# SCH_Brake_chopper_circuit_BissC.net
KiCad netlist of a schematic drawn in EasyEDA
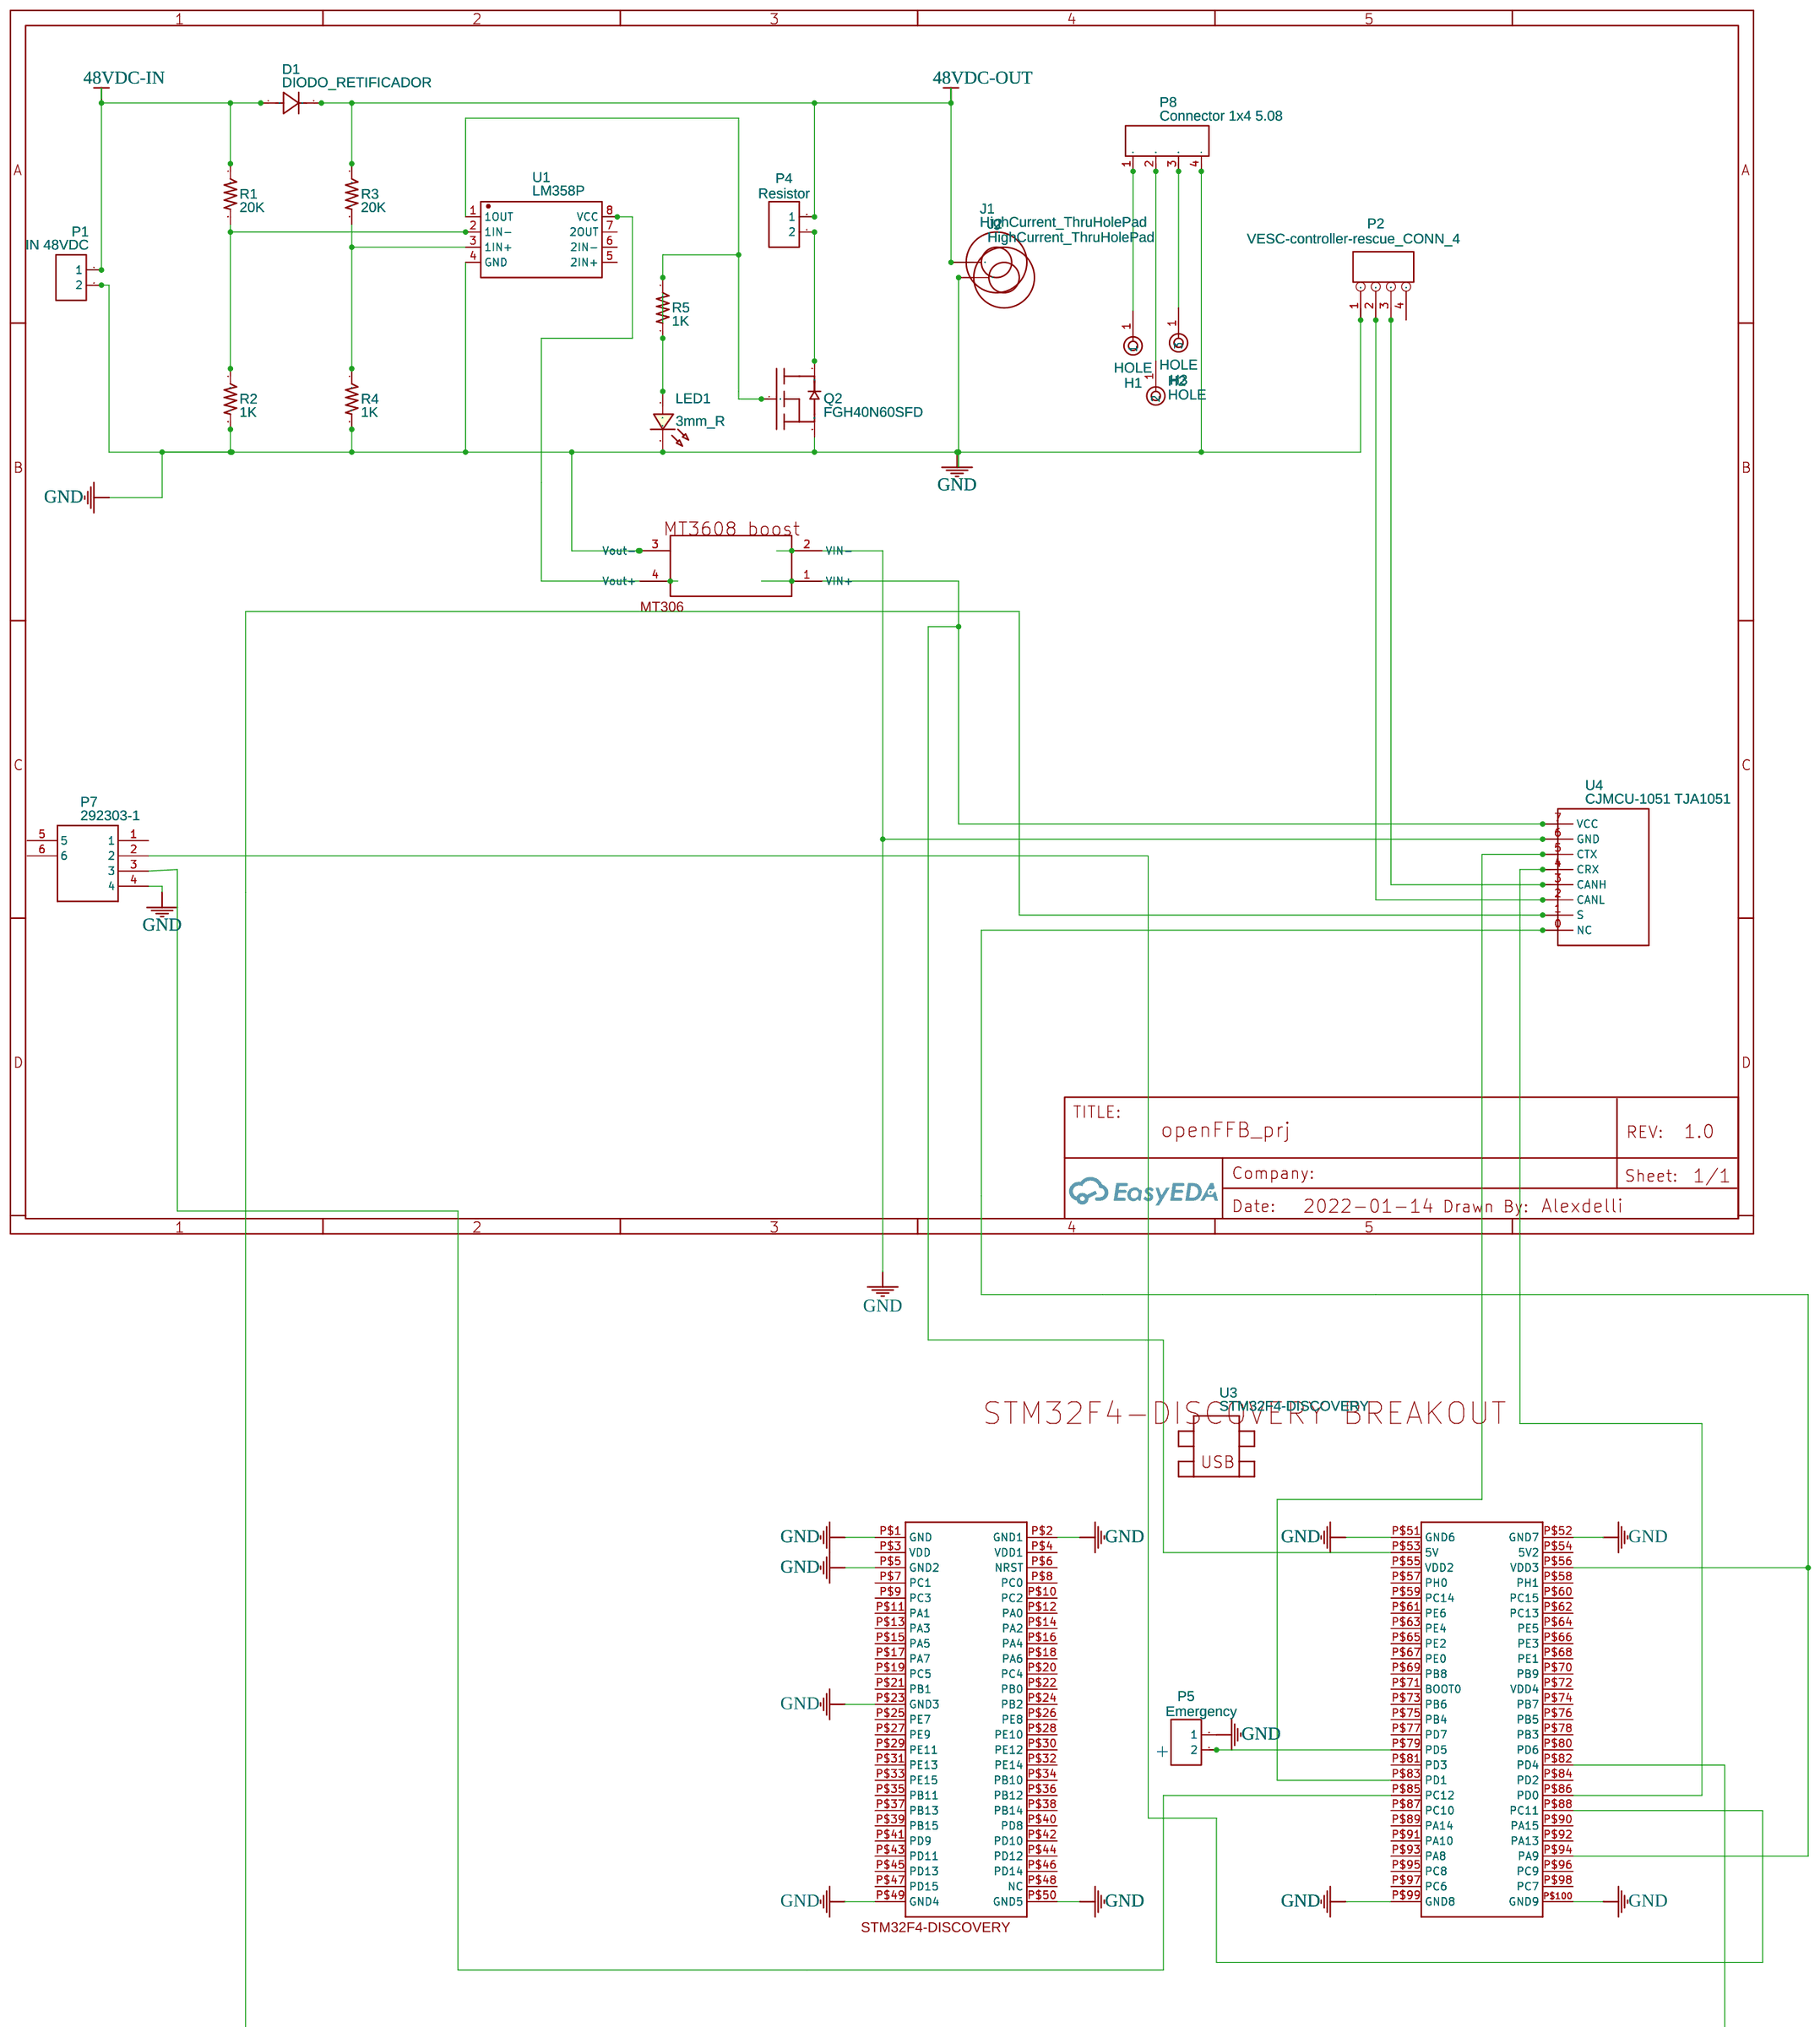
[diagram p0: schematic sheet]

(export (version "E")
  (design (tool "Eeschema 10.0.6"))
  (components
    (comp (ref "D1") (value "DIODO_RETIFICADOR") (libsource (lib "") (part "DIODO_RETIFICADOR")))
    (comp (ref "H1") (value "HOLE") (libsource (lib "") (part "HOLE_2")))
    (comp (ref "H2") (value "HOLE") (libsource (lib "") (part "HOLE")))
    (comp (ref "H3") (value "HOLE") (libsource (lib "") (part "HOLE_1")))
    (comp (ref "J1") (value "HighCurrent_ThruHolePad") (libsource (lib "") (part "HighCurrent_ThruHolePad")))
    (comp (ref "J2") (value "HighCurrent_ThruHolePad") (libsource (lib "") (part "HighCurrent_ThruHolePad")))
    (comp (ref "LED1")
      (value "3mm_R")
      (fields
        (field (name "BOM_Manufacturer Part") "204-10SDRD/S530-A3-L")
        (field (name "BOM_Supplier Part") "C84774")
      )
      (libsource (lib "") (part "LED-TH-3mm_R"))
    )
    (comp (ref "P1") (value "IN 48VDC") (libsource (lib "") (part "CONN-TH_2P-P5.08")))
    (comp (ref "P2")
      (value "VESC-controller-rescue_CONN_4")
      (libsource (lib "") (part "VESC-controller-rescue_CONN_4"))
    )
    (comp (ref "P4") (value "Resistor") (libsource (lib "") (part "CONN-TH_2P-P5.08_1")))
    (comp (ref "P5") (value "Emergency") (libsource (lib "") (part "CONN-TH_2P-P5.08_1")))
    (comp (ref "P7") (value "292303-1") (libsource (lib "") (part "292303-1")))
    (comp (ref "P8") (value "Connector 1x4 5.08") (libsource (lib "") (part "Connector 1x4 5.08")))
    (comp (ref "Q2")
      (value "FGH40N60SFD")
      (fields (field (name "BOM_Supplier Part") "C898160"))
      (libsource (lib "") (part "FGH40N60SFD"))
    )
    (comp (ref "R1") (value "20K") (libsource (lib "") (part "Resistor")))
    (comp (ref "R2") (value "1K") (libsource (lib "") (part "Resistor")))
    (comp (ref "R3") (value "20K") (libsource (lib "") (part "Resistor")))
    (comp (ref "R4") (value "1K") (libsource (lib "") (part "Resistor")))
    (comp (ref "R5") (value "1K") (libsource (lib "") (part "Resistor")))
    (comp (ref "U1")
      (value "LM358P")
      (fields (field (name "BOM_Supplier Part") "C5213"))
      (libsource (lib "") (part "LM358P"))
    )
    (comp (ref "U2") (value "mt306 boost") (libsource (lib "") (part "mt306 boost")))
    (comp (ref "U3") (value "STM32F4-DISCOVERY") (libsource (lib "") (part "STM32F4-DISCOVERY")))
    (comp (ref "U4")
      (value "CJMCU-1051 TJA1051")
      (fields (field (name "BOM_Manufacturer Part") "TJA1051"))
      (libsource (lib "") (part "CJMCU-1051 TJA1051"))
    )
  )
  (nets
    (net (code "1") (name "48VDC-IN") (class "Default")
      (node (ref "D1") (pin "A") (pinfunction "A_A") (pintype "unspecified"))
      (node (ref "P1") (pin "1") (pinfunction "1_1") (pintype "unspecified"))
      (node (ref "R1") (pin "1") (pinfunction "1_1") (pintype "unspecified"))
    )
    (net (code "2") (name "48VDC-OUT") (class "Default")
      (node (ref "D1") (pin "K") (pinfunction "K_K") (pintype "unspecified"))
      (node (ref "J1") (pin "1") (pinfunction "1_1") (pintype "unspecified"))
      (node (ref "P4") (pin "2") (pinfunction "1_2") (pintype "unspecified"))
      (node (ref "R3") (pin "1") (pinfunction "1_1") (pintype "unspecified"))
    )
    (net (code "3") (name "GND") (class "Default")
      (node (ref "J2") (pin "1") (pinfunction "1_1") (pintype "unspecified"))
      (node (ref "LED1") (pin "2") (pinfunction "2_2") (pintype "unspecified"))
      (node (ref "P1") (pin "2") (pinfunction "2_2") (pintype "unspecified"))
      (node (ref "P2") (pin "1") (pinfunction "P1_1") (pintype "unspecified"))
      (node (ref "P5") (pin "2") (pinfunction "1_2") (pintype "unspecified"))
      (node (ref "P7") (pin "4") (pinfunction "4_4") (pintype "bidirectional"))
      (node (ref "P8") (pin "4") (pinfunction "4_4") (pintype "unspecified"))
      (node (ref "Q2") (pin "3") (pinfunction "S_3") (pintype "unspecified"))
      (node (ref "R2") (pin "2") (pinfunction "2_2") (pintype "unspecified"))
      (node (ref "R4") (pin "2") (pinfunction "2_2") (pintype "unspecified"))
      (node (ref "U1") (pin "4") (pinfunction "GND_4") (pintype "unspecified"))
      (node (ref "U2") (pin "2") (pinfunction "VIN-_2") (pintype "unspecified"))
      (node (ref "U2") (pin "3") (pinfunction "Vout-_3") (pintype "unspecified"))
      (node (ref "U3") (pin "P$1") (pinfunction "GND_P$1") (pintype "unspecified"))
      (node (ref "U3") (pin "P$100") (pinfunction "GND9_P$100") (pintype "unspecified"))
      (node (ref "U3") (pin "P$2") (pinfunction "GND1_P$2") (pintype "unspecified"))
      (node (ref "U3") (pin "P$23") (pinfunction "GND3_P$23") (pintype "unspecified"))
      (node (ref "U3") (pin "P$49") (pinfunction "GND4_P$49") (pintype "unspecified"))
      (node (ref "U3") (pin "P$5") (pinfunction "GND2_P$5") (pintype "unspecified"))
      (node (ref "U3") (pin "P$50") (pinfunction "GND5_P$50") (pintype "unspecified"))
      (node (ref "U3") (pin "P$51") (pinfunction "GND6_P$51") (pintype "unspecified"))
      (node (ref "U3") (pin "P$52") (pinfunction "GND7_P$52") (pintype "unspecified"))
      (node (ref "U3") (pin "P$99") (pinfunction "GND8_P$99") (pintype "unspecified"))
      (node (ref "U4") (pin "6") (pinfunction "GND_6") (pintype "unspecified"))
    )
    (net (code "4") (name "Net-(H1-Pad1)") (class "Default")
      (node (ref "H1") (pin "1") (pinfunction "1_1") (pintype "unspecified"))
      (node (ref "P8") (pin "1") (pinfunction "1_1") (pintype "unspecified"))
    )
    (net (code "5") (name "Net-(H2-2)") (class "Default")
      (node (ref "H2") (pin "1") (pinfunction "2_1") (pintype "unspecified"))
      (node (ref "P8") (pin "2") (pinfunction "2_2") (pintype "unspecified"))
    )
    (net (code "6") (name "Net-(H3-3)") (class "Default")
      (node (ref "H3") (pin "1") (pinfunction "3_1") (pintype "unspecified"))
      (node (ref "P8") (pin "3") (pinfunction "3_3") (pintype "unspecified"))
    )
    (net (code "7") (name "Net-(LED1-Pad1)") (class "Default")
      (node (ref "LED1") (pin "1") (pinfunction "1_1") (pintype "unspecified"))
      (node (ref "R5") (pin "2") (pinfunction "2_2") (pintype "unspecified"))
    )
    (net (code "8") (name "Net-(P2-P2)") (class "Default")
      (node (ref "P2") (pin "2") (pinfunction "P2_2") (pintype "unspecified"))
      (node (ref "U4") (pin "2") (pinfunction "CANL_2") (pintype "unspecified"))
    )
    (net (code "9") (name "Net-(P2-P3)") (class "Default")
      (node (ref "P2") (pin "3") (pinfunction "P3_3") (pintype "unspecified"))
      (node (ref "U4") (pin "3") (pinfunction "CANH_3") (pintype "unspecified"))
    )
    (net (code "10") (name "Net-(P4-2)") (class "Default")
      (node (ref "P4") (pin "1") (pinfunction "2_1") (pintype "unspecified"))
      (node (ref "Q2") (pin "2") (pinfunction "D_2") (pintype "unspecified"))
    )
    (net (code "11") (name "Net-(P5-2)") (class "Default")
      (node (ref "P5") (pin "1") (pinfunction "2_1") (pintype "unspecified"))
      (node (ref "U3") (pin "P$79") (pinfunction "PD5_P$79") (pintype "unspecified"))
    )
    (net (code "12") (name "Net-(Q2-G)") (class "Default")
      (node (ref "Q2") (pin "1") (pinfunction "G_1") (pintype "unspecified"))
      (node (ref "R5") (pin "1") (pinfunction "1_1") (pintype "unspecified"))
      (node (ref "U1") (pin "1") (pinfunction "1OUT_1") (pintype "unspecified"))
    )
    (net (code "13") (name "Net-(U1-1IN+)") (class "Default")
      (node (ref "R3") (pin "2") (pinfunction "2_2") (pintype "unspecified"))
      (node (ref "R4") (pin "1") (pinfunction "1_1") (pintype "unspecified"))
      (node (ref "U1") (pin "3") (pinfunction "1IN+_3") (pintype "unspecified"))
    )
    (net (code "14") (name "Net-(U1-1IN-)") (class "Default")
      (node (ref "R1") (pin "2") (pinfunction "2_2") (pintype "unspecified"))
      (node (ref "R2") (pin "1") (pinfunction "1_1") (pintype "unspecified"))
      (node (ref "U1") (pin "2") (pinfunction "1IN-_2") (pintype "unspecified"))
    )
    (net (code "15") (name "Net-(U1-VCC)") (class "Default")
      (node (ref "U1") (pin "8") (pinfunction "VCC_8") (pintype "unspecified"))
      (node (ref "U2") (pin "4") (pinfunction "Vout+_4") (pintype "unspecified"))
    )
    (net (code "16") (name "Net-(U2-VIN+)") (class "Default")
      (node (ref "U2") (pin "1") (pinfunction "VIN+_1") (pintype "unspecified"))
      (node (ref "U3") (pin "P$53") (pinfunction "5V_P$53") (pintype "unspecified"))
      (node (ref "U4") (pin "7") (pinfunction "VCC_7") (pintype "unspecified"))
    )
    (net (code "17") (name "Net-(U3-PA9)") (class "Default")
      (node (ref "U3") (pin "P$56") (pinfunction "VDD3_P$56") (pintype "unspecified"))
      (node (ref "U3") (pin "P$94") (pinfunction "PA9_P$94") (pintype "unspecified"))
      (node (ref "U4") (pin "0") (pinfunction "NC_0") (pintype "unspecified"))
    )
    (net (code "18") (name "Net-(U3-PC11)") (class "Default")
      (node (ref "P7") (pin "2") (pinfunction "2_2") (pintype "bidirectional"))
      (node (ref "U3") (pin "P$88") (pinfunction "PC11_P$88") (pintype "unspecified"))
    )
    (net (code "19") (name "Net-(U3-PC12)") (class "Default")
      (node (ref "P7") (pin "3") (pinfunction "3_3") (pintype "bidirectional"))
      (node (ref "U3") (pin "P$85") (pinfunction "PC12_P$85") (pintype "unspecified"))
    )
    (net (code "20") (name "Net-(U3-PD0)") (class "Default")
      (node (ref "U3") (pin "P$86") (pinfunction "PD0_P$86") (pintype "unspecified"))
      (node (ref "U4") (pin "4") (pinfunction "CRX_4") (pintype "unspecified"))
    )
    (net (code "21") (name "Net-(U3-PD1)") (class "Default")
      (node (ref "U3") (pin "P$83") (pinfunction "PD1_P$83") (pintype "unspecified"))
      (node (ref "U4") (pin "5") (pinfunction "CTX_5") (pintype "unspecified"))
    )
    (net (code "22") (name "Net-(U3-PD4)") (class "Default")
      (node (ref "U3") (pin "P$82") (pinfunction "PD4_P$82") (pintype "unspecified"))
      (node (ref "U4") (pin "1") (pinfunction "S_1") (pintype "unspecified"))
    )
    (net (code "23") (name "unconnected-(P2-P4-Pad4)") (class "Default")
      (node (ref "P2") (pin "4") (pinfunction "P4_4") (pintype "unspecified"))
    )
    (net (code "24") (name "unconnected-(P7-Pad1)") (class "Default")
      (node (ref "P7") (pin "1") (pinfunction "1_1") (pintype "bidirectional"))
    )
    (net (code "25") (name "unconnected-(P7-Pad5)") (class "Default")
      (node (ref "P7") (pin "5") (pinfunction "5_5") (pintype "bidirectional"))
    )
    (net (code "26") (name "unconnected-(P7-Pad6)") (class "Default")
      (node (ref "P7") (pin "6") (pinfunction "6_6") (pintype "bidirectional"))
    )
    (net (code "27") (name "unconnected-(U1-2IN+-Pad5)") (class "Default")
      (node (ref "U1") (pin "5") (pinfunction "2IN+_5") (pintype "unspecified"))
    )
    (net (code "28") (name "unconnected-(U1-2IN--Pad6)") (class "Default")
      (node (ref "U1") (pin "6") (pinfunction "2IN-_6") (pintype "unspecified"))
    )
    (net (code "29") (name "unconnected-(U1-2OUT-Pad7)") (class "Default")
      (node (ref "U1") (pin "7") (pinfunction "2OUT_7") (pintype "unspecified"))
    )
    (net (code "30") (name "unconnected-(U3-5V2-PadP$54)") (class "Default")
      (node (ref "U3") (pin "P$54") (pinfunction "5V2_P$54") (pintype "unspecified"))
    )
    (net (code "31") (name "unconnected-(U3-BOOT0-PadP$71)") (class "Default")
      (node (ref "U3") (pin "P$71") (pinfunction "BOOT0_P$71") (pintype "unspecified"))
    )
    (net (code "32") (name "unconnected-(U3-NC-PadP$48)") (class "Default")
      (node (ref "U3") (pin "P$48") (pinfunction "NC_P$48") (pintype "unspecified"))
    )
    (net (code "33") (name "unconnected-(U3-NRST-PadP$6)") (class "Default")
      (node (ref "U3") (pin "P$6") (pinfunction "NRST_P$6") (pintype "unspecified"))
    )
    (net (code "34") (name "unconnected-(U3-PA0-PadP$12)") (class "Default")
      (node (ref "U3") (pin "P$12") (pinfunction "PA0_P$12") (pintype "unspecified"))
    )
    (net (code "35") (name "unconnected-(U3-PA1-PadP$11)") (class "Default")
      (node (ref "U3") (pin "P$11") (pinfunction "PA1_P$11") (pintype "unspecified"))
    )
    (net (code "36") (name "unconnected-(U3-PA2-PadP$14)") (class "Default")
      (node (ref "U3") (pin "P$14") (pinfunction "PA2_P$14") (pintype "unspecified"))
    )
    (net (code "37") (name "unconnected-(U3-PA3-PadP$13)") (class "Default")
      (node (ref "U3") (pin "P$13") (pinfunction "PA3_P$13") (pintype "unspecified"))
    )
    (net (code "38") (name "unconnected-(U3-PA4-PadP$16)") (class "Default")
      (node (ref "U3") (pin "P$16") (pinfunction "PA4_P$16") (pintype "unspecified"))
    )
    (net (code "39") (name "unconnected-(U3-PA5-PadP$15)") (class "Default")
      (node (ref "U3") (pin "P$15") (pinfunction "PA5_P$15") (pintype "unspecified"))
    )
    (net (code "40") (name "unconnected-(U3-PA6-PadP$18)") (class "Default")
      (node (ref "U3") (pin "P$18") (pinfunction "PA6_P$18") (pintype "unspecified"))
    )
    (net (code "41") (name "unconnected-(U3-PA7-PadP$17)") (class "Default")
      (node (ref "U3") (pin "P$17") (pinfunction "PA7_P$17") (pintype "unspecified"))
    )
    (net (code "42") (name "unconnected-(U3-PA8-PadP$93)") (class "Default")
      (node (ref "U3") (pin "P$93") (pinfunction "PA8_P$93") (pintype "unspecified"))
    )
    (net (code "43") (name "unconnected-(U3-PA10-PadP$91)") (class "Default")
      (node (ref "U3") (pin "P$91") (pinfunction "PA10_P$91") (pintype "unspecified"))
    )
    (net (code "44") (name "unconnected-(U3-PA13-PadP$92)") (class "Default")
      (node (ref "U3") (pin "P$92") (pinfunction "PA13_P$92") (pintype "unspecified"))
    )
    (net (code "45") (name "unconnected-(U3-PA14-PadP$89)") (class "Default")
      (node (ref "U3") (pin "P$89") (pinfunction "PA14_P$89") (pintype "unspecified"))
    )
    (net (code "46") (name "unconnected-(U3-PA15-PadP$90)") (class "Default")
      (node (ref "U3") (pin "P$90") (pinfunction "PA15_P$90") (pintype "unspecified"))
    )
    (net (code "47") (name "unconnected-(U3-PB0-PadP$22)") (class "Default")
      (node (ref "U3") (pin "P$22") (pinfunction "PB0_P$22") (pintype "unspecified"))
    )
    (net (code "48") (name "unconnected-(U3-PB1-PadP$21)") (class "Default")
      (node (ref "U3") (pin "P$21") (pinfunction "PB1_P$21") (pintype "unspecified"))
    )
    (net (code "49") (name "unconnected-(U3-PB2-PadP$24)") (class "Default")
      (node (ref "U3") (pin "P$24") (pinfunction "PB2_P$24") (pintype "unspecified"))
    )
    (net (code "50") (name "unconnected-(U3-PB3-PadP$78)") (class "Default")
      (node (ref "U3") (pin "P$78") (pinfunction "PB3_P$78") (pintype "unspecified"))
    )
    (net (code "51") (name "unconnected-(U3-PB4-PadP$75)") (class "Default")
      (node (ref "U3") (pin "P$75") (pinfunction "PB4_P$75") (pintype "unspecified"))
    )
    (net (code "52") (name "unconnected-(U3-PB5-PadP$76)") (class "Default")
      (node (ref "U3") (pin "P$76") (pinfunction "PB5_P$76") (pintype "unspecified"))
    )
    (net (code "53") (name "unconnected-(U3-PB6-PadP$73)") (class "Default")
      (node (ref "U3") (pin "P$73") (pinfunction "PB6_P$73") (pintype "unspecified"))
    )
    (net (code "54") (name "unconnected-(U3-PB7-PadP$74)") (class "Default")
      (node (ref "U3") (pin "P$74") (pinfunction "PB7_P$74") (pintype "unspecified"))
    )
    (net (code "55") (name "unconnected-(U3-PB8-PadP$69)") (class "Default")
      (node (ref "U3") (pin "P$69") (pinfunction "PB8_P$69") (pintype "unspecified"))
    )
    (net (code "56") (name "unconnected-(U3-PB9-PadP$70)") (class "Default")
      (node (ref "U3") (pin "P$70") (pinfunction "PB9_P$70") (pintype "unspecified"))
    )
    (net (code "57") (name "unconnected-(U3-PB10-PadP$34)") (class "Default")
      (node (ref "U3") (pin "P$34") (pinfunction "PB10_P$34") (pintype "unspecified"))
    )
    (net (code "58") (name "unconnected-(U3-PB11-PadP$35)") (class "Default")
      (node (ref "U3") (pin "P$35") (pinfunction "PB11_P$35") (pintype "unspecified"))
    )
    (net (code "59") (name "unconnected-(U3-PB12-PadP$36)") (class "Default")
      (node (ref "U3") (pin "P$36") (pinfunction "PB12_P$36") (pintype "unspecified"))
    )
    (net (code "60") (name "unconnected-(U3-PB13-PadP$37)") (class "Default")
      (node (ref "U3") (pin "P$37") (pinfunction "PB13_P$37") (pintype "unspecified"))
    )
    (net (code "61") (name "unconnected-(U3-PB14-PadP$38)") (class "Default")
      (node (ref "U3") (pin "P$38") (pinfunction "PB14_P$38") (pintype "unspecified"))
    )
    (net (code "62") (name "unconnected-(U3-PB15-PadP$39)") (class "Default")
      (node (ref "U3") (pin "P$39") (pinfunction "PB15_P$39") (pintype "unspecified"))
    )
    (net (code "63") (name "unconnected-(U3-PC0-PadP$8)") (class "Default")
      (node (ref "U3") (pin "P$8") (pinfunction "PC0_P$8") (pintype "unspecified"))
    )
    (net (code "64") (name "unconnected-(U3-PC1-PadP$7)") (class "Default")
      (node (ref "U3") (pin "P$7") (pinfunction "PC1_P$7") (pintype "unspecified"))
    )
    (net (code "65") (name "unconnected-(U3-PC2-PadP$10)") (class "Default")
      (node (ref "U3") (pin "P$10") (pinfunction "PC2_P$10") (pintype "unspecified"))
    )
    (net (code "66") (name "unconnected-(U3-PC3-PadP$9)") (class "Default")
      (node (ref "U3") (pin "P$9") (pinfunction "PC3_P$9") (pintype "unspecified"))
    )
    (net (code "67") (name "unconnected-(U3-PC4-PadP$20)") (class "Default")
      (node (ref "U3") (pin "P$20") (pinfunction "PC4_P$20") (pintype "unspecified"))
    )
    (net (code "68") (name "unconnected-(U3-PC5-PadP$19)") (class "Default")
      (node (ref "U3") (pin "P$19") (pinfunction "PC5_P$19") (pintype "unspecified"))
    )
    (net (code "69") (name "unconnected-(U3-PC6-PadP$97)") (class "Default")
      (node (ref "U3") (pin "P$97") (pinfunction "PC6_P$97") (pintype "unspecified"))
    )
    (net (code "70") (name "unconnected-(U3-PC7-PadP$98)") (class "Default")
      (node (ref "U3") (pin "P$98") (pinfunction "PC7_P$98") (pintype "unspecified"))
    )
    (net (code "71") (name "unconnected-(U3-PC8-PadP$95)") (class "Default")
      (node (ref "U3") (pin "P$95") (pinfunction "PC8_P$95") (pintype "unspecified"))
    )
    (net (code "72") (name "unconnected-(U3-PC9-PadP$96)") (class "Default")
      (node (ref "U3") (pin "P$96") (pinfunction "PC9_P$96") (pintype "unspecified"))
    )
    (net (code "73") (name "unconnected-(U3-PC10-PadP$87)") (class "Default")
      (node (ref "U3") (pin "P$87") (pinfunction "PC10_P$87") (pintype "unspecified"))
    )
    (net (code "74") (name "unconnected-(U3-PC13-PadP$62)") (class "Default")
      (node (ref "U3") (pin "P$62") (pinfunction "PC13_P$62") (pintype "unspecified"))
    )
    (net (code "75") (name "unconnected-(U3-PC14-PadP$59)") (class "Default")
      (node (ref "U3") (pin "P$59") (pinfunction "PC14_P$59") (pintype "unspecified"))
    )
    (net (code "76") (name "unconnected-(U3-PC15-PadP$60)") (class "Default")
      (node (ref "U3") (pin "P$60") (pinfunction "PC15_P$60") (pintype "unspecified"))
    )
    (net (code "77") (name "unconnected-(U3-PD2-PadP$84)") (class "Default")
      (node (ref "U3") (pin "P$84") (pinfunction "PD2_P$84") (pintype "unspecified"))
    )
    (net (code "78") (name "unconnected-(U3-PD3-PadP$81)") (class "Default")
      (node (ref "U3") (pin "P$81") (pinfunction "PD3_P$81") (pintype "unspecified"))
    )
    (net (code "79") (name "unconnected-(U3-PD6-PadP$80)") (class "Default")
      (node (ref "U3") (pin "P$80") (pinfunction "PD6_P$80") (pintype "unspecified"))
    )
    (net (code "80") (name "unconnected-(U3-PD7-PadP$77)") (class "Default")
      (node (ref "U3") (pin "P$77") (pinfunction "PD7_P$77") (pintype "unspecified"))
    )
    (net (code "81") (name "unconnected-(U3-PD8-PadP$40)") (class "Default")
      (node (ref "U3") (pin "P$40") (pinfunction "PD8_P$40") (pintype "unspecified"))
    )
    (net (code "82") (name "unconnected-(U3-PD9-PadP$41)") (class "Default")
      (node (ref "U3") (pin "P$41") (pinfunction "PD9_P$41") (pintype "unspecified"))
    )
    (net (code "83") (name "unconnected-(U3-PD10-PadP$42)") (class "Default")
      (node (ref "U3") (pin "P$42") (pinfunction "PD10_P$42") (pintype "unspecified"))
    )
    (net (code "84") (name "unconnected-(U3-PD11-PadP$43)") (class "Default")
      (node (ref "U3") (pin "P$43") (pinfunction "PD11_P$43") (pintype "unspecified"))
    )
    (net (code "85") (name "unconnected-(U3-PD12-PadP$44)") (class "Default")
      (node (ref "U3") (pin "P$44") (pinfunction "PD12_P$44") (pintype "unspecified"))
    )
    (net (code "86") (name "unconnected-(U3-PD13-PadP$45)") (class "Default")
      (node (ref "U3") (pin "P$45") (pinfunction "PD13_P$45") (pintype "unspecified"))
    )
    (net (code "87") (name "unconnected-(U3-PD14-PadP$46)") (class "Default")
      (node (ref "U3") (pin "P$46") (pinfunction "PD14_P$46") (pintype "unspecified"))
    )
    (net (code "88") (name "unconnected-(U3-PD15-PadP$47)") (class "Default")
      (node (ref "U3") (pin "P$47") (pinfunction "PD15_P$47") (pintype "unspecified"))
    )
    (net (code "89") (name "unconnected-(U3-PE0-PadP$67)") (class "Default")
      (node (ref "U3") (pin "P$67") (pinfunction "PE0_P$67") (pintype "unspecified"))
    )
    (net (code "90") (name "unconnected-(U3-PE1-PadP$68)") (class "Default")
      (node (ref "U3") (pin "P$68") (pinfunction "PE1_P$68") (pintype "unspecified"))
    )
    (net (code "91") (name "unconnected-(U3-PE2-PadP$65)") (class "Default")
      (node (ref "U3") (pin "P$65") (pinfunction "PE2_P$65") (pintype "unspecified"))
    )
    (net (code "92") (name "unconnected-(U3-PE3-PadP$66)") (class "Default")
      (node (ref "U3") (pin "P$66") (pinfunction "PE3_P$66") (pintype "unspecified"))
    )
    (net (code "93") (name "unconnected-(U3-PE4-PadP$63)") (class "Default")
      (node (ref "U3") (pin "P$63") (pinfunction "PE4_P$63") (pintype "unspecified"))
    )
    (net (code "94") (name "unconnected-(U3-PE5-PadP$64)") (class "Default")
      (node (ref "U3") (pin "P$64") (pinfunction "PE5_P$64") (pintype "unspecified"))
    )
    (net (code "95") (name "unconnected-(U3-PE6-PadP$61)") (class "Default")
      (node (ref "U3") (pin "P$61") (pinfunction "PE6_P$61") (pintype "unspecified"))
    )
    (net (code "96") (name "unconnected-(U3-PE7-PadP$25)") (class "Default")
      (node (ref "U3") (pin "P$25") (pinfunction "PE7_P$25") (pintype "unspecified"))
    )
    (net (code "97") (name "unconnected-(U3-PE8-PadP$26)") (class "Default")
      (node (ref "U3") (pin "P$26") (pinfunction "PE8_P$26") (pintype "unspecified"))
    )
    (net (code "98") (name "unconnected-(U3-PE9-PadP$27)") (class "Default")
      (node (ref "U3") (pin "P$27") (pinfunction "PE9_P$27") (pintype "unspecified"))
    )
    (net (code "99") (name "unconnected-(U3-PE10-PadP$28)") (class "Default")
      (node (ref "U3") (pin "P$28") (pinfunction "PE10_P$28") (pintype "unspecified"))
    )
    (net (code "100") (name "unconnected-(U3-PE11-PadP$29)") (class "Default")
      (node (ref "U3") (pin "P$29") (pinfunction "PE11_P$29") (pintype "unspecified"))
    )
    (net (code "101") (name "unconnected-(U3-PE12-PadP$30)") (class "Default")
      (node (ref "U3") (pin "P$30") (pinfunction "PE12_P$30") (pintype "unspecified"))
    )
    (net (code "102") (name "unconnected-(U3-PE13-PadP$31)") (class "Default")
      (node (ref "U3") (pin "P$31") (pinfunction "PE13_P$31") (pintype "unspecified"))
    )
    (net (code "103") (name "unconnected-(U3-PE14-PadP$32)") (class "Default")
      (node (ref "U3") (pin "P$32") (pinfunction "PE14_P$32") (pintype "unspecified"))
    )
    (net (code "104") (name "unconnected-(U3-PE15-PadP$33)") (class "Default")
      (node (ref "U3") (pin "P$33") (pinfunction "PE15_P$33") (pintype "unspecified"))
    )
    (net (code "105") (name "unconnected-(U3-PH0-PadP$57)") (class "Default")
      (node (ref "U3") (pin "P$57") (pinfunction "PH0_P$57") (pintype "unspecified"))
    )
    (net (code "106") (name "unconnected-(U3-PH1-PadP$58)") (class "Default")
      (node (ref "U3") (pin "P$58") (pinfunction "PH1_P$58") (pintype "unspecified"))
    )
    (net (code "107") (name "unconnected-(U3-VDD-PadP$3)") (class "Default")
      (node (ref "U3") (pin "P$3") (pinfunction "VDD_P$3") (pintype "unspecified"))
    )
    (net (code "108") (name "unconnected-(U3-VDD1-PadP$4)") (class "Default")
      (node (ref "U3") (pin "P$4") (pinfunction "VDD1_P$4") (pintype "unspecified"))
    )
    (net (code "109") (name "unconnected-(U3-VDD2-PadP$55)") (class "Default")
      (node (ref "U3") (pin "P$55") (pinfunction "VDD2_P$55") (pintype "unspecified"))
    )
    (net (code "110") (name "unconnected-(U3-VDD4-PadP$72)") (class "Default")
      (node (ref "U3") (pin "P$72") (pinfunction "VDD4_P$72") (pintype "unspecified"))
    )
  )
)
